# BrushlessPowerSupply.net
KiCad netlist of a schematic drawn in EasyEDA Pro
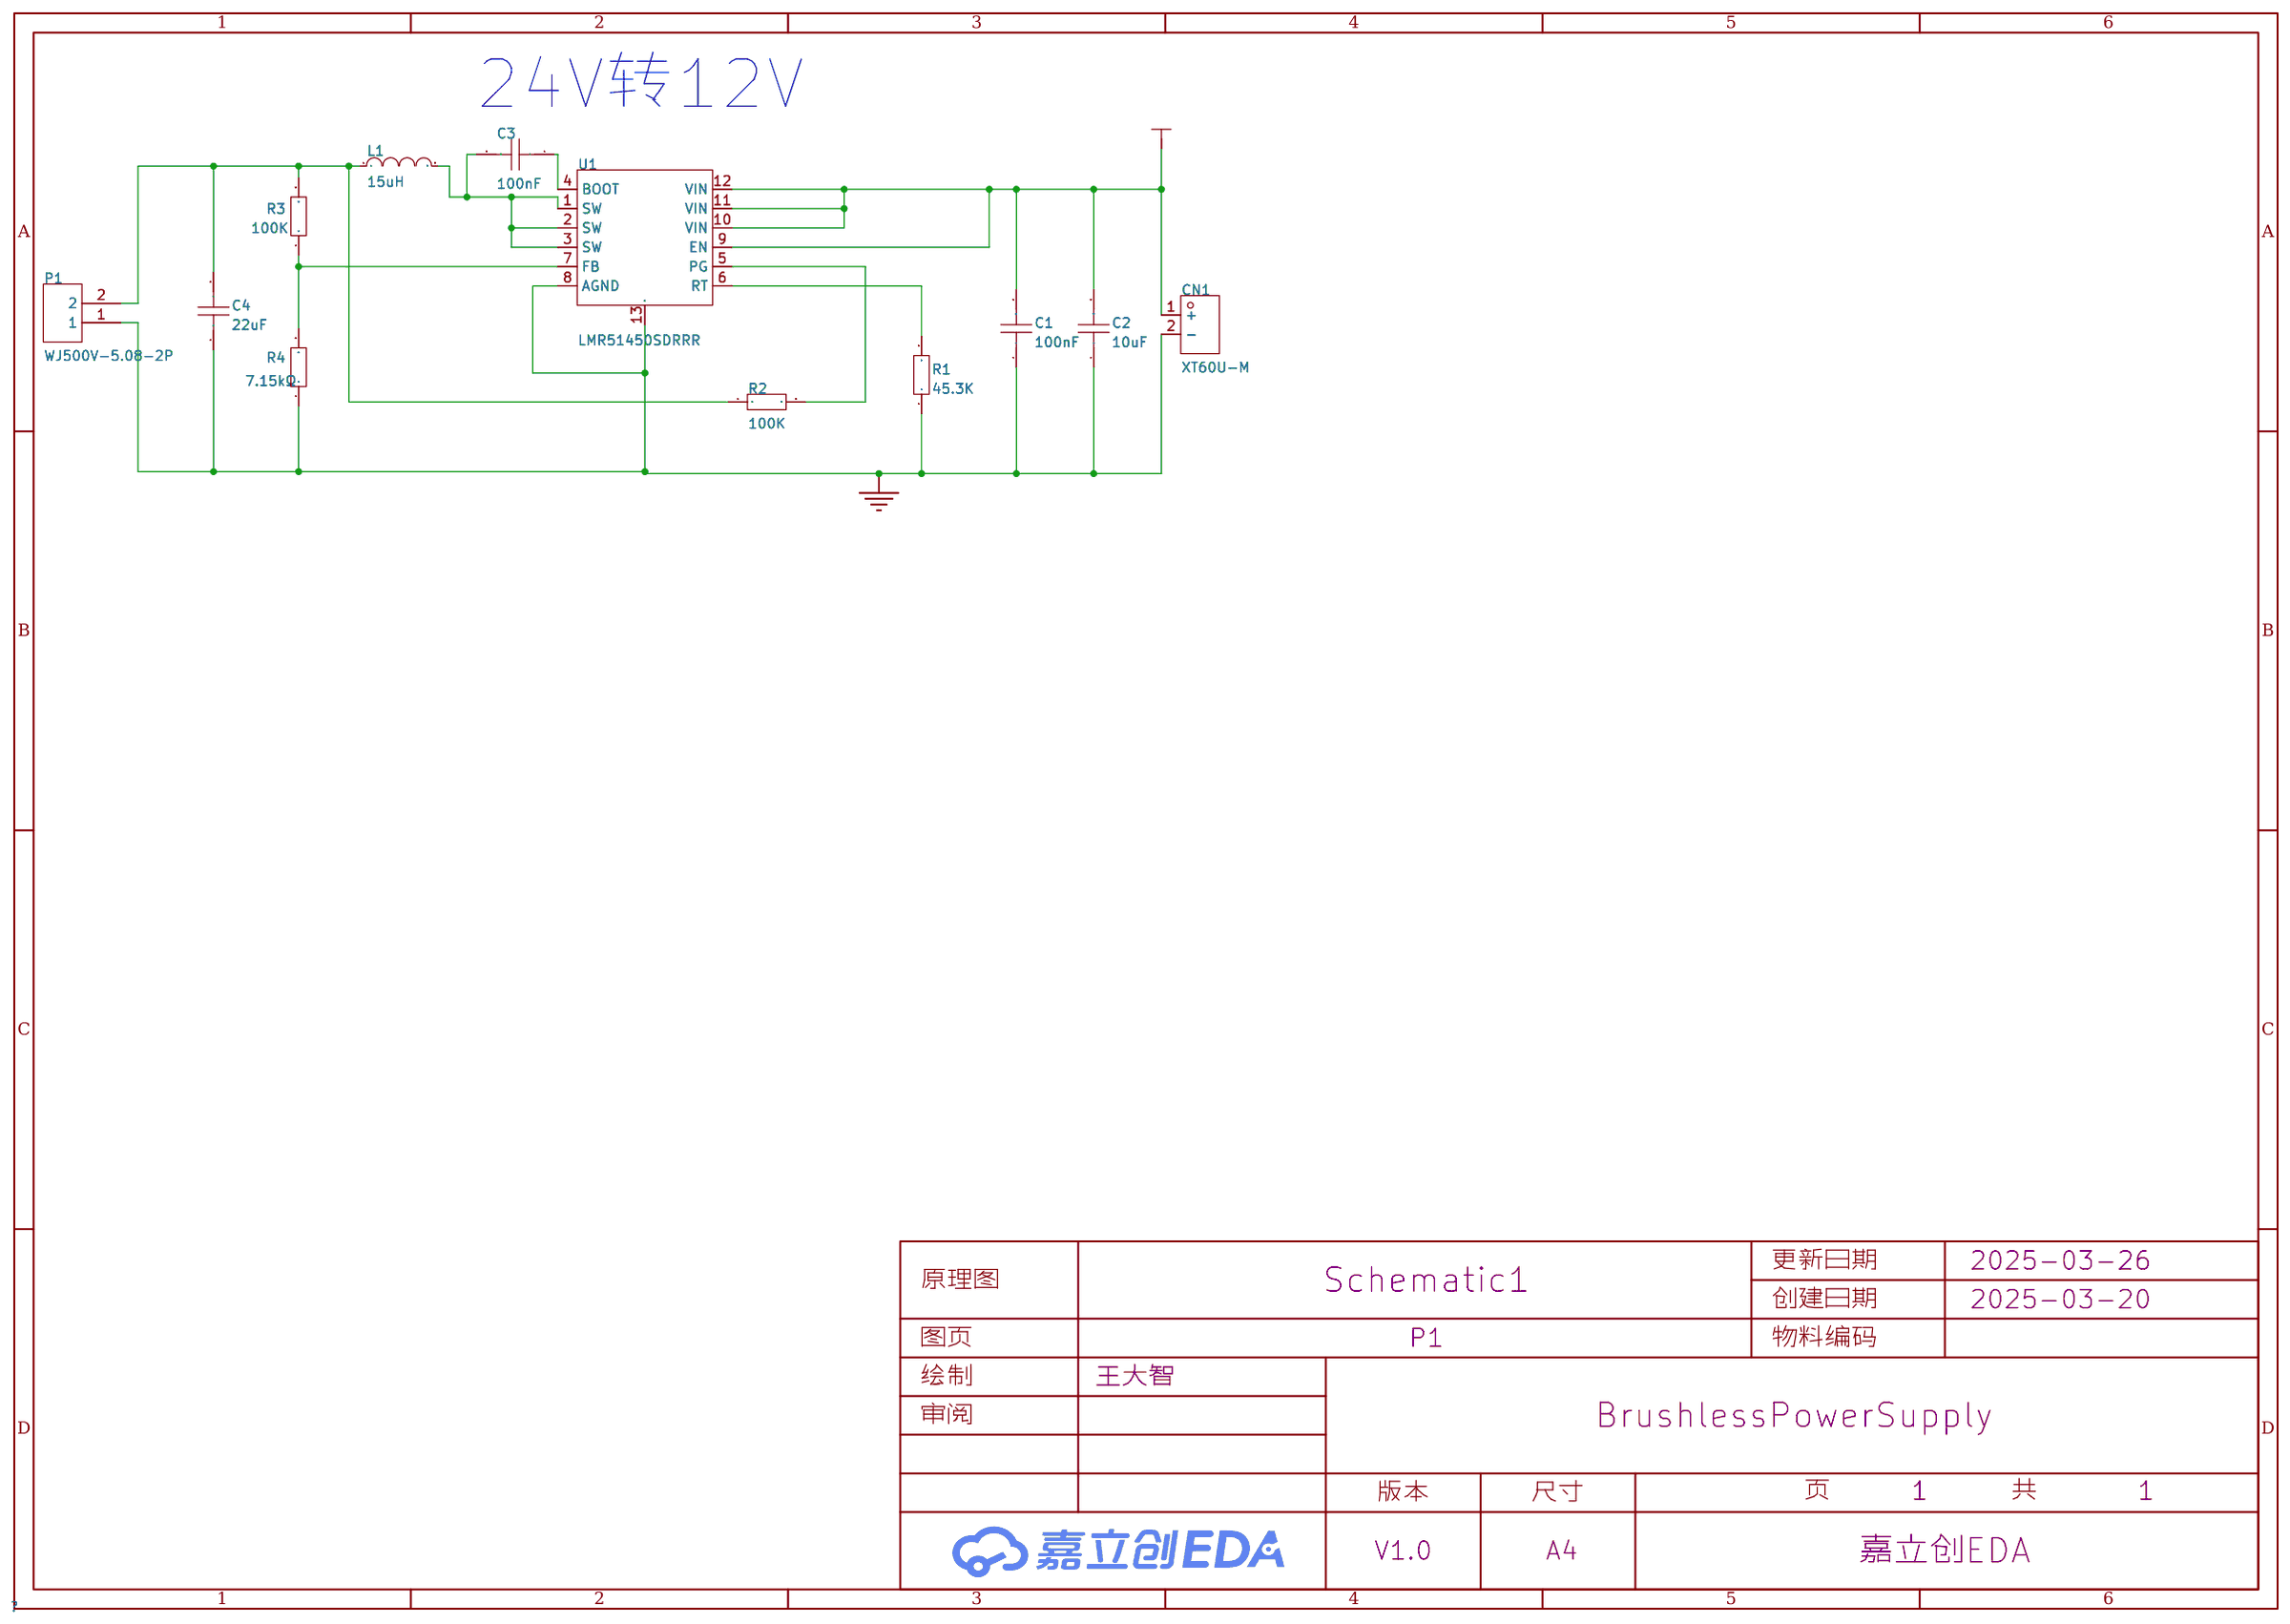
[diagram p0: schematic sheet]

(export (version "E")
  (design (tool "Eeschema 10.0.6"))
  (components
    (comp (ref "C1")
      (value "100nF")
      (footprint "easyedapro:C0603")
      (libsource (lib "easyedapro") (part "CapAcitance"))
    )
    (comp (ref "C2")
      (value "10uF")
      (footprint "easyedapro:C0603")
      (libsource (lib "easyedapro") (part "CapAcitance"))
    )
    (comp (ref "C3")
      (value "100nF")
      (footprint "easyedapro:C0603")
      (libsource (lib "easyedapro") (part "CapAcitance"))
    )
    (comp (ref "C4")
      (value "22uF")
      (footprint "easyedapro:C0603")
      (libsource (lib "easyedapro") (part "CapAcitance"))
    )
    (comp (ref "CN1")
      (value "XT60U-M")
      (footprint "easyedapro:CONN-TH_XT60U-M")
      (description "类别:-;类型1:-;")
      (fields (field (name "Manufacturer") "AMASS(艾迈斯)"))
      (libsource (lib "easyedapro") (part "XT60U-M"))
    )
    (comp (ref "L1")
      (value "15uH")
      (footprint "easyedapro:L0603")
      (libsource (lib "easyedapro") (part "SDFL1608S100KTF"))
    )
    (comp (ref "P1")
      (value "WJ500V-5.08-2P")
      (footprint "easyedapro:CONN-TH_2P-P5.00_WJ500V-5.08-2P")
      (fields (field (name "Manufacturer") "KANGNEX(康奈克斯电气)"))
      (libsource (lib "easyedapro") (part "WJ500V-5.08-2P-14-00A"))
    )
    (comp (ref "R1")
      (value "45.3K")
      (footprint "easyedapro:R0603")
      (libsource (lib "easyedapro") (part "电阻"))
    )
    (comp (ref "R2") (value "100K") (footprint "easyedapro:R0603") (libsource (lib "easyedapro") (part "电阻")))
    (comp (ref "R3") (value "100K") (footprint "easyedapro:R0603") (libsource (lib "easyedapro") (part "电阻")))
    (comp (ref "R4")
      (value "7.15kΩ")
      (footprint "easyedapro:R0603")
      (fields
        (field (name "Manufacturer Part") "0603WAF7151T5E")
        (field (name "Manufacturer") "UNI-ROYAL(厚声)")
      )
      (libsource (lib "easyedapro") (part "电阻"))
    )
    (comp (ref "U1")
      (value "LMR51450SDRRR")
      (footprint "easyedapro:WSON-12_L3.0-W3.0-P0.50-TL-EP-2")
      (description "功能类型:降压型;输出类型:可调;输入电压:4V~36V;输出电压:800mV~28V;输出电流(最大值):5A;")
      (fields (field (name "Manufacturer") "TI(德州仪器)"))
      (libsource (lib "easyedapro") (part "LMR51450SDRRR"))
    )
  )
  (nets
    (net (code "1") (name "+24V") (class "Default")
      (node (ref "C1") (pin "2") (pinfunction "2_2") (pintype "input"))
      (node (ref "C2") (pin "2") (pinfunction "2_2") (pintype "input"))
      (node (ref "CN1") (pin "1") (pinfunction "+_1") (pintype "unspecified"))
      (node (ref "U1") (pin "10") (pinfunction "VIN_10") (pintype "unspecified"))
      (node (ref "U1") (pin "11") (pinfunction "VIN_11") (pintype "unspecified"))
      (node (ref "U1") (pin "12") (pinfunction "VIN_12") (pintype "unspecified"))
      (node (ref "U1") (pin "9") (pinfunction "EN_9") (pintype "unspecified"))
    )
    (net (code "2") (name "GND") (class "Default")
      (node (ref "C1") (pin "1") (pinfunction "1_1") (pintype "input"))
      (node (ref "C2") (pin "1") (pinfunction "1_1") (pintype "input"))
      (node (ref "C4") (pin "1") (pinfunction "1_1") (pintype "input"))
      (node (ref "CN1") (pin "2") (pinfunction "-_2") (pintype "unspecified"))
      (node (ref "P1") (pin "1") (pinfunction "1_1") (pintype "unspecified"))
      (node (ref "R1") (pin "1") (pinfunction "1_1") (pintype "input"))
      (node (ref "R4") (pin "1") (pinfunction "1_1") (pintype "input"))
      (node (ref "U1") (pin "13") (pinfunction "EP_13") (pintype "unspecified"))
      (node (ref "U1") (pin "8") (pinfunction "AGND_8") (pintype "unspecified"))
    )
    (net (code "3") (name "Net-(C3-Pad2)") (class "Default")
      (node (ref "C3") (pin "2") (pinfunction "2_2") (pintype "input"))
      (node (ref "L1") (pin "2") (pinfunction "2_2") (pintype "unspecified"))
      (node (ref "U1") (pin "1") (pinfunction "SW_1") (pintype "unspecified"))
      (node (ref "U1") (pin "2") (pinfunction "SW_2") (pintype "unspecified"))
      (node (ref "U1") (pin "3") (pinfunction "SW_3") (pintype "unspecified"))
    )
    (net (code "4") (name "Net-(C4-Pad2)") (class "Default")
      (node (ref "C4") (pin "2") (pinfunction "2_2") (pintype "input"))
      (node (ref "L1") (pin "1") (pinfunction "1_1") (pintype "unspecified"))
      (node (ref "P1") (pin "2") (pinfunction "2_2") (pintype "unspecified"))
      (node (ref "R2") (pin "1") (pinfunction "1_1") (pintype "input"))
      (node (ref "R3") (pin "2") (pinfunction "2_2") (pintype "input"))
    )
    (net (code "5") (name "Net-(U1-BOOT)") (class "Default")
      (node (ref "C3") (pin "1") (pinfunction "1_1") (pintype "input"))
      (node (ref "U1") (pin "4") (pinfunction "BOOT_4") (pintype "unspecified"))
    )
    (net (code "6") (name "Net-(U1-FB)") (class "Default")
      (node (ref "R3") (pin "1") (pinfunction "1_1") (pintype "input"))
      (node (ref "R4") (pin "2") (pinfunction "2_2") (pintype "input"))
      (node (ref "U1") (pin "7") (pinfunction "FB_7") (pintype "unspecified"))
    )
    (net (code "7") (name "Net-(U1-PG)") (class "Default")
      (node (ref "R2") (pin "2") (pinfunction "2_2") (pintype "input"))
      (node (ref "U1") (pin "5") (pinfunction "PG_5") (pintype "unspecified"))
    )
    (net (code "8") (name "Net-(U1-RT)") (class "Default")
      (node (ref "R1") (pin "2") (pinfunction "2_2") (pintype "input"))
      (node (ref "U1") (pin "6") (pinfunction "RT_6") (pintype "unspecified"))
    )
  )
)
